# BLE.net
KiCad netlist of a schematic drawn in Altium Designer
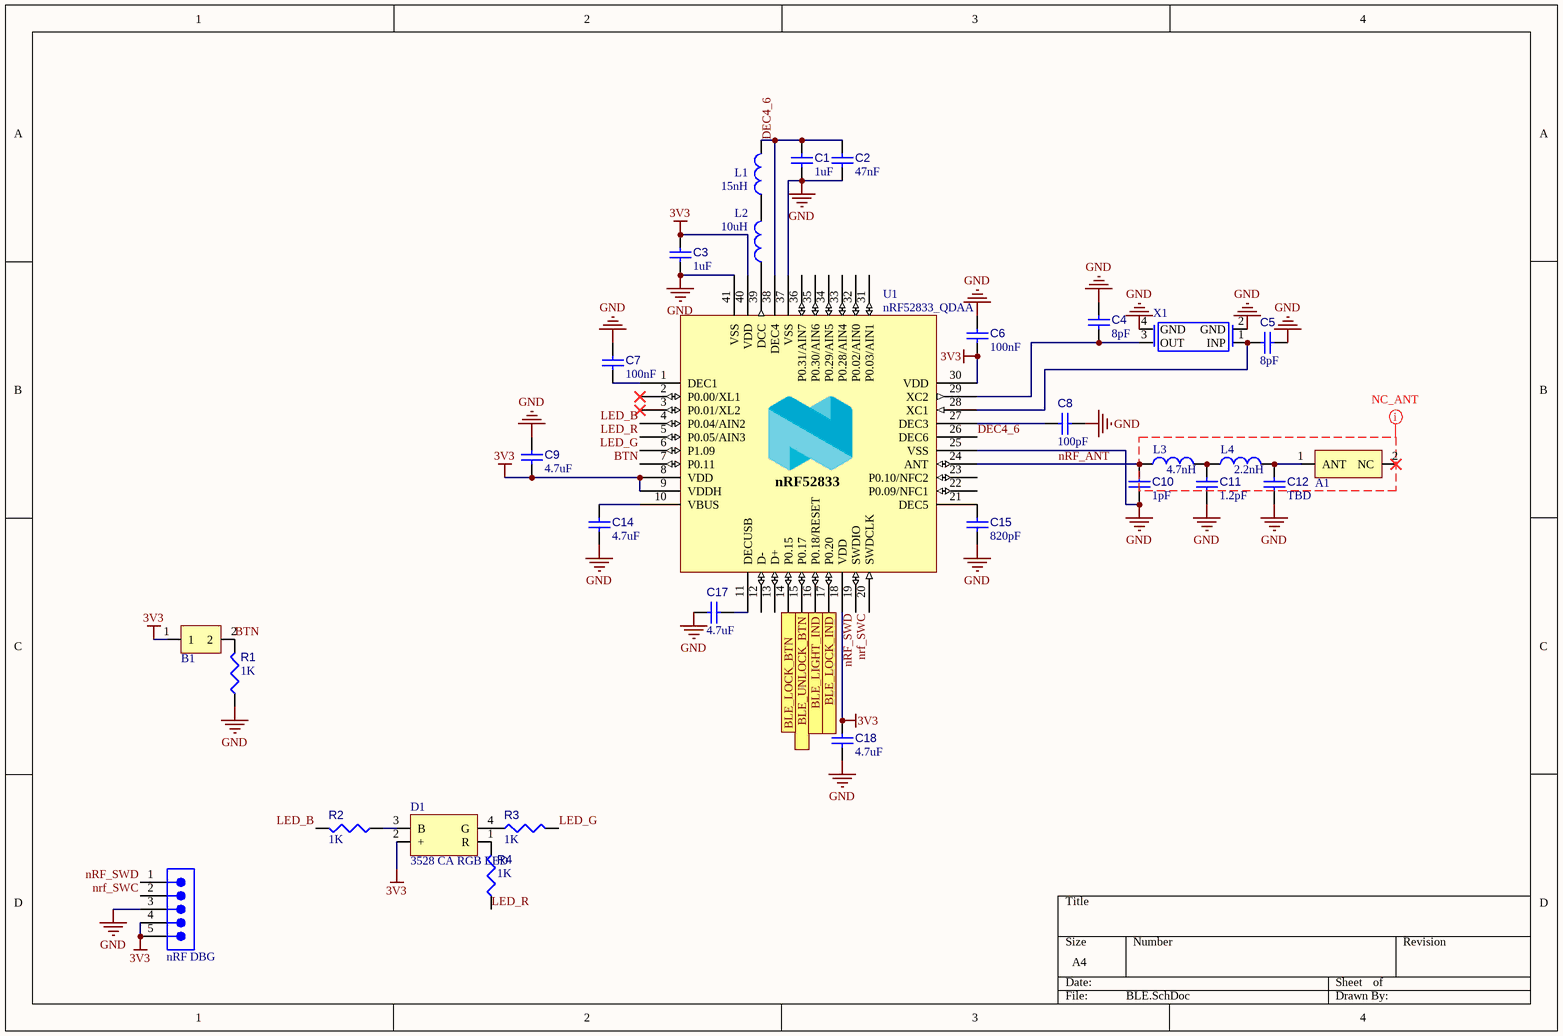
[diagram p0: BLE.SchDoc]

(export (version "E")
  (design (tool "Eeschema 10.0.6"))
  (components
    (comp (ref "A1")
      (value "RFANT3216120A1T")
      (footprint "INDC3216X13L")
      (description "2450Mhz 50Mhz Ceramic Antenna")
      (libsource (lib "Database") (part "RFANT3216120A1T"))
    )
    (comp (ref "B1")
      (value "B3U-1000P")
      (footprint "2.5*4 BTN")
      (description "2.5x4 Ultra-small Tactile Switch")
      (libsource (lib "Database") (part "2 Terminal BTN"))
    )
    (comp (ref "C1")
      (value "1uF")
      (footprint "CAPC1005X55X25LL05T05")
      (description "Non-Polarized Capacitor Symbol")
      (fields (field (name "TOLERANCE") "10%") (field (name "Comment") "CL05A105KA5NQNC"))
      (libsource (lib "Database") (part "Non-Polarized Capacitor Sym"))
    )
    (comp (ref "C2")
      (value "47nF")
      (footprint "CAPC1005X55X25LL05T05")
      (description "Non-Polarized Capacitor Symbol")
      (fields (field (name "TOLERANCE") "10%") (field (name "Comment") "CL05B473KB5VPNC"))
      (libsource (lib "Database") (part "Non-Polarized Capacitor Sym"))
    )
    (comp (ref "C3")
      (value "1uF")
      (footprint "CAPC1005X55X25LL05T05")
      (description "Non-Polarized Capacitor Symbol")
      (fields (field (name "TOLERANCE") "10%") (field (name "Comment") "CL05A105KA5NQNC"))
      (libsource (lib "Database") (part "Non-Polarized Capacitor Sym"))
    )
    (comp (ref "C4")
      (value "8pF")
      (footprint "CAPC1005X55X25LL05T05")
      (description "Non-Polarized Capacitor Symbol")
      (fields (field (name "TOLERANCE") "0.5pF") (field (name "Comment") "CL05C080DB5NNNC"))
      (libsource (lib "Database") (part "Non-Polarized Capacitor Sym"))
    )
    (comp (ref "C5")
      (value "8pF")
      (footprint "CAPC1005X55X25LL05T05")
      (description "Non-Polarized Capacitor Symbol")
      (fields (field (name "TOLERANCE") "0.5pF") (field (name "Comment") "CL05C080DB5NNNC"))
      (libsource (lib "Database") (part "Non-Polarized Capacitor Sym"))
    )
    (comp (ref "C6")
      (value "100nF")
      (footprint "CAPC1005X55X25LL05T05")
      (description "Non-Polarized Capacitor Symbol")
      (fields (field (name "TOLERANCE") "10%") (field (name "Comment") "CL05B104KB5NNNC"))
      (libsource (lib "Database") (part "Non-Polarized Capacitor Sym"))
    )
    (comp (ref "C7")
      (value "100nF")
      (footprint "CAPC1005X55X25LL05T05")
      (description "Non-Polarized Capacitor Symbol")
      (fields (field (name "TOLERANCE") "10%") (field (name "Comment") "CL05B104KB5NNNC"))
      (libsource (lib "Database") (part "Non-Polarized Capacitor Sym"))
    )
    (comp (ref "C8")
      (value "100pF")
      (footprint "CAPC1005X55X25LL05T05")
      (description "Non-Polarized Capacitor Symbol")
      (fields (field (name "TOLERANCE") "5%") (field (name "Comment") "CL05C101JB5NNNC"))
      (libsource (lib "Database") (part "Non-Polarized Capacitor Sym"))
    )
    (comp (ref "C9")
      (value "4.7uF")
      (footprint "CAPC1005X55X25LL05T05")
      (description "Non-Polarized Capacitor Symbol")
      (fields (field (name "TOLERANCE") "20%") (field (name "Comment") "CL05A475MQ5NRNC"))
      (libsource (lib "Database") (part "Non-Polarized Capacitor Sym"))
    )
    (comp (ref "C10")
      (value "1pF")
      (footprint "CAPC1005X55X25LL05T05")
      (description "Non-Polarized Capacitor Symbol")
      (fields (field (name "TOLERANCE") "0.25pF") (field (name "Comment") "CL05C010CB5NNNC"))
      (libsource (lib "Database") (part "Non-Polarized Capacitor Sym"))
    )
    (comp (ref "C11")
      (value "1.2pF")
      (footprint "CAPC1005X55X25LL05T05")
      (description "Non-Polarized Capacitor Symbol")
      (fields (field (name "TOLERANCE") "0.1pF") (field (name "Comment") "CL05C1R2BB5NNNC"))
      (libsource (lib "Database") (part "Non-Polarized Capacitor Sym"))
    )
    (comp (ref "C12")
      (value "TBD")
      (footprint "CAPC1005X55X25LL05T05")
      (description "Non-Polarized Capacitor Symbol")
      (fields (field (name "Comment") "0402 Capacitor"))
      (libsource (lib "Database") (part "Non-Polarized Capacitor Sym"))
    )
    (comp (ref "C14")
      (value "4.7uF")
      (footprint "CAPC1005X55X25LL05T05")
      (description "Non-Polarized Capacitor Symbol")
      (fields (field (name "TOLERANCE") "20%") (field (name "Comment") "CL05A475MQ5NRNC"))
      (libsource (lib "Database") (part "Non-Polarized Capacitor Sym"))
    )
    (comp (ref "C15")
      (value "820pF")
      (footprint "CAPC1005X55X25LL05T05")
      (description "Non-Polarized Capacitor Symbol")
      (fields (field (name "TOLERANCE") "10%") (field (name "Comment") "CL05B821KB5NNNC"))
      (libsource (lib "Database") (part "Non-Polarized Capacitor Sym"))
    )
    (comp (ref "C17")
      (value "4.7uF")
      (footprint "CAPC1005X55X25LL05T05")
      (description "Non-Polarized Capacitor Symbol")
      (fields (field (name "TOLERANCE") "20%") (field (name "Comment") "CL05A475MQ5NRNC"))
      (libsource (lib "Database") (part "Non-Polarized Capacitor Sym"))
    )
    (comp (ref "C18")
      (value "4.7uF")
      (footprint "CAPC1005X55X25LL05T05")
      (description "Non-Polarized Capacitor Symbol")
      (fields (field (name "TOLERANCE") "20%") (field (name "Comment") "CL05A475MQ5NRNC"))
      (libsource (lib "Database") (part "Non-Polarized Capacitor Sym"))
    )
    (comp (ref "D1")
      (value "3528 CA RGB LED")
      (footprint "3528 CA RGB LED")
      (description "3528 Common Anode RGB LED")
      (libsource (lib "Database") (part "RGB LED CA"))
    )
    (comp (ref "L1")
      (value "15nH")
      (footprint "INDC1005X06L")
      (description "HF inductor")
      (fields (field (name "Comment") "SDCL1005C15NJTDF"))
      (libsource (lib "Database") (part "2 Terminal Inductor"))
    )
    (comp (ref "L2")
      (value "10uH")
      (footprint "INDC1608X10L")
      (description "Chip Coil inductor 50mA 20% 10uH")
      (fields (field (name "Comment") "LQM18FN100M00D"))
      (libsource (lib "Database") (part "2 Terminal Inductor"))
    )
    (comp (ref "L3")
      (value "4.7nH")
      (footprint "INDC1005X06L")
      (description "4.7nH ±0.3nH 300mA HF")
      (fields (field (name "Comment") "SDCL1005C4N7STDF"))
      (libsource (lib "Database") (part "2 Terminal Inductor"))
    )
    (comp (ref "L4")
      (value "2.2nH")
      (footprint "INDC1005X06L")
      (description "HF inductor")
      (fields (field (name "Comment") "SDCL1005C2N2STDF"))
      (libsource (lib "Database") (part "2 Terminal Inductor"))
    )
    (comp (ref "nRF DBG")
      (value "653005114822")
      (footprint "653005114822")
      (description "WR-WTB THT Male Vertical Shrouded Header, pitch 1.25mm, 5pins")
      (fields (field (name "MANUFACTURER") "Wurth Elektronik"))
      (libsource (lib "WE - Electromechanical Components") (part "Header_Male_1R_05P"))
    )
    (comp (ref "R1")
      (value "1K")
      (footprint "RESC1005X40X25LL05T05")
      (description "0402 Chip Resistor")
      (fields (field (name "Comment") "1K 0402"))
      (libsource (lib "Database") (part "Chip Resistor"))
    )
    (comp (ref "R2")
      (value "1K")
      (footprint "RESC1608X55X25LL10T15")
      (description "0603 Chip Resistor")
      (fields (field (name "Comment") "1K 0603"))
      (libsource (lib "Database") (part "Chip Resistor"))
    )
    (comp (ref "R3")
      (value "1K")
      (footprint "RESC1608X55X25LL10T15")
      (description "0603 Chip Resistor")
      (fields (field (name "Comment") "1K 0603"))
      (libsource (lib "Database") (part "Chip Resistor"))
    )
    (comp (ref "R4")
      (value "1K")
      (footprint "RESC1608X55X25LL10T15")
      (description "0603 Chip Resistor")
      (fields (field (name "Comment") "1K 0603"))
      (libsource (lib "Database") (part "Chip Resistor"))
    )
    (comp (ref "U1")
      (value "nRF52833_QDAA")
      (footprint "QFN40P500X500X50_HS-41N")
      (description "Multi-protocol Bluetooth Low Energy, IEEE 802.15.4, ANT and 2.4GHz proprietary system-on-chip")
      (libsource (lib "Database") (part "nRF52833_QDAA"))
    )
    (comp (ref "X1")
      (value "X201632MKB4SI")
      (footprint "XTAL_2016")
      (description "32MHz ±10ppm 8pF")
      (libsource (lib "Database") (part "4Pin Crystal"))
    )
  )
  (nets
    (net (code "1") (name "/BLE_LIGHT_IND") (class "Default")
      (node (ref "U1") (pin "16") (pinfunction "P0.18/RESET_16") (pintype "bidirectional"))
    )
    (net (code "2") (name "/BLE_LOCK_BTN") (class "Default")
      (node (ref "U1") (pin "14") (pinfunction "P0.15_14") (pintype "bidirectional"))
    )
    (net (code "3") (name "/BLE_LOCK_IND") (class "Default")
      (node (ref "U1") (pin "17") (pinfunction "P0.20_17") (pintype "bidirectional"))
    )
    (net (code "4") (name "/BLE_UNLOCK_BTN") (class "Default")
      (node (ref "U1") (pin "15") (pinfunction "P0.17_15") (pintype "bidirectional"))
    )
    (net (code "5") (name "/BTN") (class "Default")
      (node (ref "B1") (pin "2") (pinfunction "2_2") (pintype "passive"))
      (node (ref "R1") (pin "2") (pinfunction "2_2") (pintype "passive"))
      (node (ref "U1") (pin "7") (pinfunction "P0.11_7") (pintype "bidirectional"))
    )
    (net (code "6") (name "/DEC4_6") (class "Default")
      (node (ref "C1") (pin "2") (pinfunction "2_2") (pintype "passive"))
      (node (ref "C2") (pin "2") (pinfunction "2_2") (pintype "passive"))
      (node (ref "L1") (pin "2") (pinfunction "2_2") (pintype "passive"))
      (node (ref "U1") (pin "26") (pinfunction "DEC6_26") (pintype "power_in"))
      (node (ref "U1") (pin "38") (pinfunction "DEC4_38") (pintype "power_in"))
    )
    (net (code "7") (name "/LED_B") (class "Default")
      (node (ref "R2") (pin "2") (pinfunction "2_2") (pintype "passive"))
      (node (ref "U1") (pin "4") (pinfunction "P0.04/AIN2_4") (pintype "bidirectional"))
    )
    (net (code "8") (name "/LED_G") (class "Default")
      (node (ref "R3") (pin "2") (pinfunction "2_2") (pintype "passive"))
      (node (ref "U1") (pin "6") (pinfunction "P1.09_6") (pintype "bidirectional"))
    )
    (net (code "9") (name "/LED_R") (class "Default")
      (node (ref "R4") (pin "1") (pinfunction "1_1") (pintype "passive"))
      (node (ref "U1") (pin "5") (pinfunction "P0.05/AIN3_5") (pintype "bidirectional"))
    )
    (net (code "10") (name "/nRF_ANT") (class "Default")
      (node (ref "C10") (pin "2") (pinfunction "2_2") (pintype "passive"))
      (node (ref "L3") (pin "1") (pinfunction "1_1") (pintype "passive"))
      (node (ref "U1") (pin "24") (pinfunction "ANT_24") (pintype "bidirectional"))
    )
    (net (code "11") (name "/nRF_SWD") (class "Default")
      (node (ref "U1") (pin "19") (pinfunction "SWDIO_19") (pintype "bidirectional"))
      (node (ref "nRF DBG") (pin "1") (pinfunction "1_1") (pintype "passive"))
    )
    (net (code "12") (name "/nrf_SWC") (class "Default")
      (node (ref "U1") (pin "20") (pinfunction "SWDCLK_20") (pintype "input"))
      (node (ref "nRF DBG") (pin "2") (pinfunction "2_2") (pintype "passive"))
    )
    (net (code "13") (name "3V3") (class "Default")
      (node (ref "B1") (pin "1") (pinfunction "1_1") (pintype "passive"))
      (node (ref "C18") (pin "1") (pinfunction "1_1") (pintype "passive"))
      (node (ref "C3") (pin "2") (pinfunction "2_2") (pintype "passive"))
      (node (ref "C6") (pin "1") (pinfunction "1_1") (pintype "passive"))
      (node (ref "C9") (pin "1") (pinfunction "1_1") (pintype "passive"))
      (node (ref "D1") (pin "2") (pinfunction "+_2") (pintype "passive"))
      (node (ref "U1") (pin "18") (pinfunction "VDD_18") (pintype "power_in"))
      (node (ref "U1") (pin "30") (pinfunction "VDD_30") (pintype "power_in"))
      (node (ref "U1") (pin "40") (pinfunction "VDD_40") (pintype "power_in"))
      (node (ref "U1") (pin "8") (pinfunction "VDD_8") (pintype "power_in"))
      (node (ref "U1") (pin "9") (pinfunction "VDDH_9") (pintype "power_in"))
      (node (ref "nRF DBG") (pin "4") (pinfunction "4_4") (pintype "passive"))
      (node (ref "nRF DBG") (pin "5") (pinfunction "5_5") (pintype "passive"))
    )
    (net (code "14") (name "GND") (class "Default")
      (node (ref "C1") (pin "1") (pinfunction "1_1") (pintype "passive"))
      (node (ref "C10") (pin "1") (pinfunction "1_1") (pintype "passive"))
      (node (ref "C11") (pin "1") (pinfunction "1_1") (pintype "passive"))
      (node (ref "C12") (pin "1") (pinfunction "1_1") (pintype "passive"))
      (node (ref "C14") (pin "1") (pinfunction "1_1") (pintype "passive"))
      (node (ref "C15") (pin "1") (pinfunction "1_1") (pintype "passive"))
      (node (ref "C17") (pin "1") (pinfunction "1_1") (pintype "passive"))
      (node (ref "C18") (pin "2") (pinfunction "2_2") (pintype "passive"))
      (node (ref "C2") (pin "1") (pinfunction "1_1") (pintype "passive"))
      (node (ref "C3") (pin "1") (pinfunction "1_1") (pintype "passive"))
      (node (ref "C4") (pin "2") (pinfunction "2_2") (pintype "passive"))
      (node (ref "C5") (pin "1") (pinfunction "1_1") (pintype "passive"))
      (node (ref "C6") (pin "2") (pinfunction "2_2") (pintype "passive"))
      (node (ref "C7") (pin "2") (pinfunction "2_2") (pintype "passive"))
      (node (ref "C8") (pin "2") (pinfunction "2_2") (pintype "passive"))
      (node (ref "C9") (pin "2") (pinfunction "2_2") (pintype "passive"))
      (node (ref "R1") (pin "1") (pinfunction "1_1") (pintype "passive"))
      (node (ref "U1") (pin "25") (pinfunction "VSS_25") (pintype "power_in"))
      (node (ref "U1") (pin "37") (pinfunction "VSS_37") (pintype "power_in"))
      (node (ref "U1") (pin "41") (pinfunction "VSS_41") (pintype "power_in"))
      (node (ref "X1") (pin "2") (pinfunction "GND_2") (pintype "passive"))
      (node (ref "X1") (pin "4") (pinfunction "GND_4") (pintype "passive"))
      (node (ref "nRF DBG") (pin "3") (pinfunction "3_3") (pintype "passive"))
    )
    (net (code "15") (name "Net-(A1-ANT)") (class "Default")
      (node (ref "A1") (pin "1") (pinfunction "ANT_1") (pintype "passive"))
      (node (ref "C12") (pin "2") (pinfunction "2_2") (pintype "passive"))
      (node (ref "L4") (pin "2") (pinfunction "2_2") (pintype "passive"))
    )
    (net (code "16") (name "Net-(C11-Pad2)") (class "Default")
      (node (ref "C11") (pin "2") (pinfunction "2_2") (pintype "passive"))
      (node (ref "L3") (pin "2") (pinfunction "2_2") (pintype "passive"))
      (node (ref "L4") (pin "1") (pinfunction "1_1") (pintype "passive"))
    )
    (net (code "17") (name "Net-(D1-B)") (class "Default")
      (node (ref "D1") (pin "3") (pinfunction "B_3") (pintype "passive"))
      (node (ref "R2") (pin "1") (pinfunction "1_1") (pintype "passive"))
    )
    (net (code "18") (name "Net-(D1-G)") (class "Default")
      (node (ref "D1") (pin "4") (pinfunction "G_4") (pintype "passive"))
      (node (ref "R3") (pin "1") (pinfunction "1_1") (pintype "passive"))
    )
    (net (code "19") (name "Net-(D1-R)") (class "Default")
      (node (ref "D1") (pin "1") (pinfunction "R_1") (pintype "passive"))
      (node (ref "R4") (pin "2") (pinfunction "2_2") (pintype "passive"))
    )
    (net (code "20") (name "Net-(L1-Pad1)") (class "Default")
      (node (ref "L1") (pin "1") (pinfunction "1_1") (pintype "passive"))
      (node (ref "L2") (pin "2") (pinfunction "2_2") (pintype "passive"))
    )
    (net (code "21") (name "Net-(U1-DCC)") (class "Default")
      (node (ref "L2") (pin "1") (pinfunction "1_1") (pintype "passive"))
      (node (ref "U1") (pin "39") (pinfunction "DCC_39") (pintype "output"))
    )
    (net (code "22") (name "Net-(U1-DEC1)") (class "Default")
      (node (ref "C7") (pin "1") (pinfunction "1_1") (pintype "passive"))
      (node (ref "U1") (pin "1") (pinfunction "DEC1_1") (pintype "power_in"))
    )
    (net (code "23") (name "Net-(U1-DEC3)") (class "Default")
      (node (ref "C8") (pin "1") (pinfunction "1_1") (pintype "passive"))
      (node (ref "U1") (pin "27") (pinfunction "DEC3_27") (pintype "power_in"))
    )
    (net (code "24") (name "Net-(U1-DEC5)") (class "Default")
      (node (ref "C15") (pin "2") (pinfunction "2_2") (pintype "passive"))
      (node (ref "U1") (pin "21") (pinfunction "DEC5_21") (pintype "power_in"))
    )
    (net (code "25") (name "Net-(U1-DECUSB)") (class "Default")
      (node (ref "C17") (pin "2") (pinfunction "2_2") (pintype "passive"))
      (node (ref "U1") (pin "11") (pinfunction "DECUSB_11") (pintype "power_in"))
    )
    (net (code "26") (name "Net-(U1-VBUS)") (class "Default")
      (node (ref "C14") (pin "2") (pinfunction "2_2") (pintype "passive"))
      (node (ref "U1") (pin "10") (pinfunction "VBUS_10") (pintype "power_in"))
    )
    (net (code "27") (name "Net-(U1-XC1)") (class "Default")
      (node (ref "C5") (pin "2") (pinfunction "2_2") (pintype "passive"))
      (node (ref "U1") (pin "28") (pinfunction "XC1_28") (pintype "input"))
      (node (ref "X1") (pin "1") (pinfunction "INP_1") (pintype "passive"))
    )
    (net (code "28") (name "Net-(U1-XC2)") (class "Default")
      (node (ref "C4") (pin "1") (pinfunction "1_1") (pintype "passive"))
      (node (ref "U1") (pin "29") (pinfunction "XC2_29") (pintype "output"))
      (node (ref "X1") (pin "3") (pinfunction "OUT_3") (pintype "passive"))
    )
    (net (code "29") (name "unconnected-(A1-NC-Pad2)") (class "Default")
      (node (ref "A1") (pin "2") (pinfunction "NC_2") (pintype "passive+no_connect"))
    )
    (net (code "30") (name "unconnected-(U1-D+-Pad13)") (class "Default")
      (node (ref "U1") (pin "13") (pinfunction "D+_13") (pintype "bidirectional"))
    )
    (net (code "31") (name "unconnected-(U1-D--Pad12)") (class "Default")
      (node (ref "U1") (pin "12") (pinfunction "D-_12") (pintype "bidirectional"))
    )
    (net (code "32") (name "unconnected-(U1-P0.00{slash}XL1-Pad2)") (class "Default")
      (node (ref "U1") (pin "2") (pinfunction "P0.00/XL1_2") (pintype "bidirectional+no_connect"))
    )
    (net (code "33") (name "unconnected-(U1-P0.01{slash}XL2-Pad3)") (class "Default")
      (node (ref "U1") (pin "3") (pinfunction "P0.01/XL2_3") (pintype "bidirectional+no_connect"))
    )
    (net (code "34") (name "unconnected-(U1-P0.02{slash}AIN0-Pad32)") (class "Default")
      (node (ref "U1") (pin "32") (pinfunction "P0.02/AIN0_32") (pintype "bidirectional"))
    )
    (net (code "35") (name "unconnected-(U1-P0.03{slash}AIN1-Pad31)") (class "Default")
      (node (ref "U1") (pin "31") (pinfunction "P0.03/AIN1_31") (pintype "bidirectional"))
    )
    (net (code "36") (name "unconnected-(U1-P0.09{slash}NFC1-Pad22)") (class "Default")
      (node (ref "U1") (pin "22") (pinfunction "P0.09/NFC1_22") (pintype "bidirectional"))
    )
    (net (code "37") (name "unconnected-(U1-P0.10{slash}NFC2-Pad23)") (class "Default")
      (node (ref "U1") (pin "23") (pinfunction "P0.10/NFC2_23") (pintype "bidirectional"))
    )
    (net (code "38") (name "unconnected-(U1-P0.28{slash}AIN4-Pad33)") (class "Default")
      (node (ref "U1") (pin "33") (pinfunction "P0.28/AIN4_33") (pintype "bidirectional"))
    )
    (net (code "39") (name "unconnected-(U1-P0.29{slash}AIN5-Pad34)") (class "Default")
      (node (ref "U1") (pin "34") (pinfunction "P0.29/AIN5_34") (pintype "bidirectional"))
    )
    (net (code "40") (name "unconnected-(U1-P0.30{slash}AIN6-Pad35)") (class "Default")
      (node (ref "U1") (pin "35") (pinfunction "P0.30/AIN6_35") (pintype "bidirectional"))
    )
    (net (code "41") (name "unconnected-(U1-P0.31{slash}AIN7-Pad36)") (class "Default")
      (node (ref "U1") (pin "36") (pinfunction "P0.31/AIN7_36") (pintype "bidirectional"))
    )
  )
)
